# Sheet1.net
KiCad netlist of a schematic drawn in Altium Designer
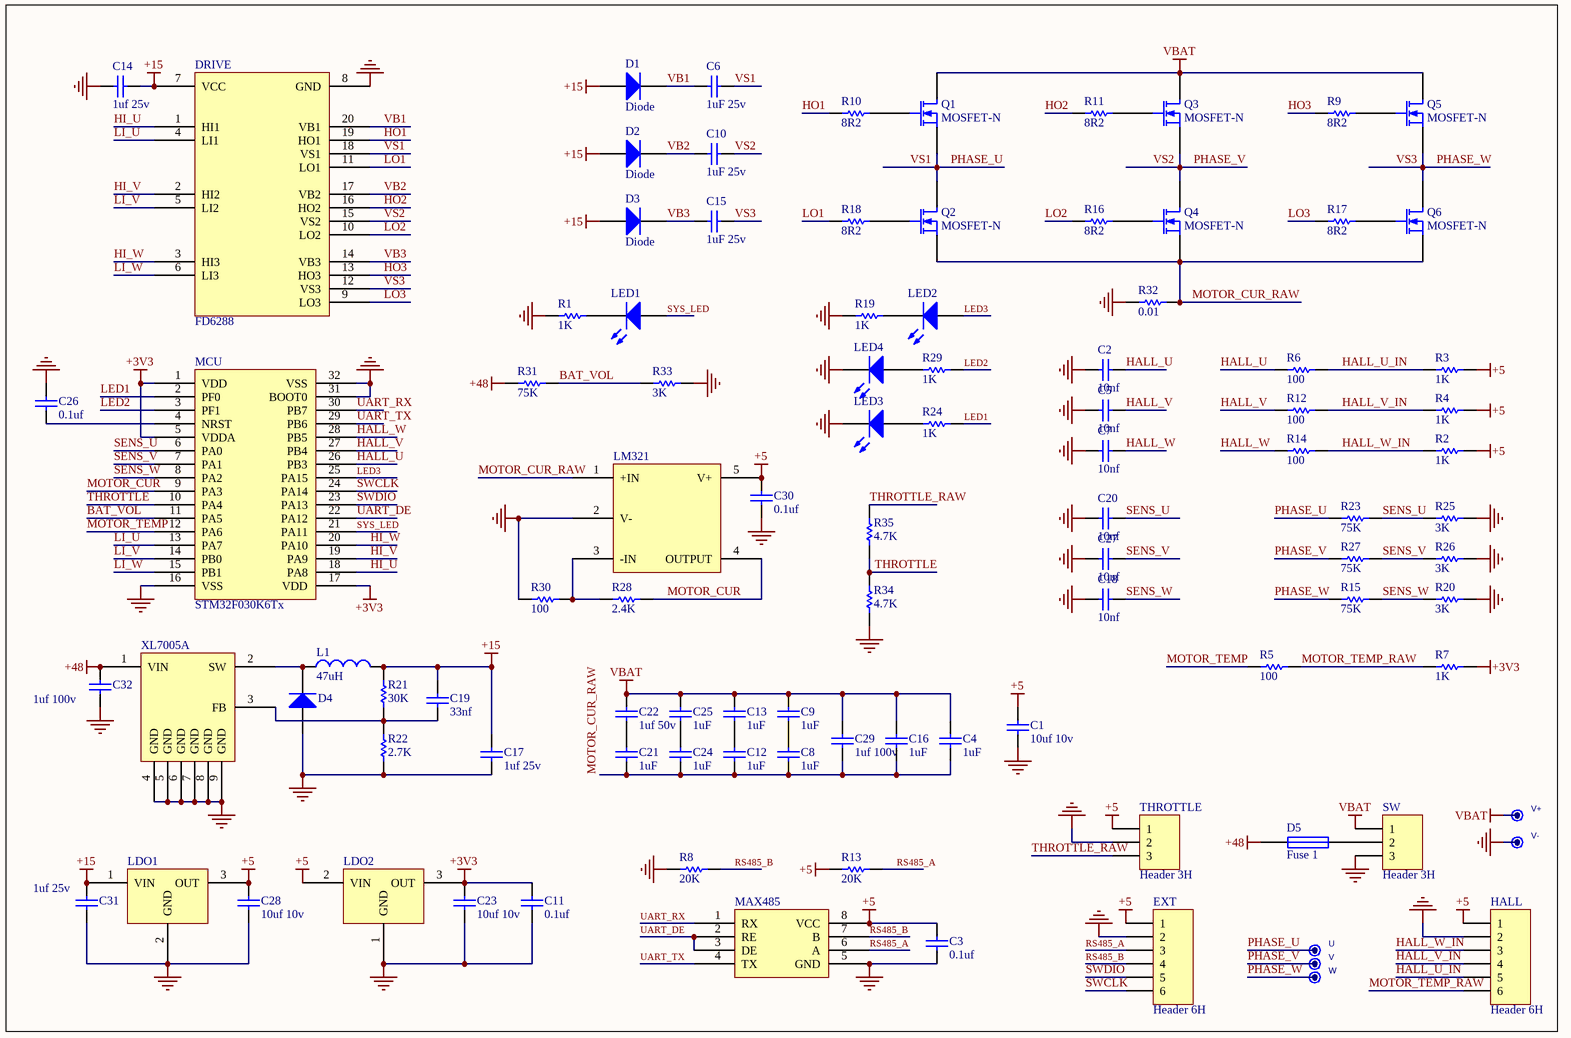
[diagram p0: Sheet1.SchDoc]

(export (version "E")
  (design (tool "Eeschema 10.0.6"))
  (components
    (comp (ref "C1")
      (value "10uf 10v")
      (footprint "0603")
      (description "Capacitor")
      (fields (field (name "Comment") "Cap") (field (name "PUBLISHER") "Altium Limited"))
      (libsource (lib "Miscellaneous Devices") (part "Cap"))
    )
    (comp (ref "C2")
      (value "10nf")
      (footprint "0603")
      (description "Capacitor")
      (fields (field (name "Comment") "Cap") (field (name "PUBLISHER") "Altium Limited"))
      (libsource (lib "Miscellaneous Devices") (part "Cap"))
    )
    (comp (ref "C3")
      (value "0.1uf")
      (footprint "0603")
      (description "Capacitor")
      (fields (field (name "Comment") "Cap") (field (name "PUBLISHER") "Altium Limited"))
      (libsource (lib "Miscellaneous Devices") (part "Cap"))
    )
    (comp (ref "C4")
      (value "1uF")
      (footprint "0603")
      (description "Capacitor")
      (fields (field (name "Comment") "Cap") (field (name "PUBLISHER") "Altium Limited"))
      (libsource (lib "Miscellaneous Devices") (part "Cap"))
    )
    (comp (ref "C5")
      (value "10nf")
      (footprint "0603")
      (description "Capacitor")
      (fields (field (name "Comment") "Cap") (field (name "PUBLISHER") "Altium Limited"))
      (libsource (lib "Miscellaneous Devices") (part "Cap"))
    )
    (comp (ref "C6")
      (value "1uF 25v")
      (footprint "0603")
      (description "Capacitor")
      (fields (field (name "Comment") "Cap") (field (name "PUBLISHER") "Altium Limited"))
      (libsource (lib "Miscellaneous Devices") (part "Cap"))
    )
    (comp (ref "C7")
      (value "10nf")
      (footprint "0603")
      (description "Capacitor")
      (fields (field (name "Comment") "Cap") (field (name "PUBLISHER") "Altium Limited"))
      (libsource (lib "Miscellaneous Devices") (part "Cap"))
    )
    (comp (ref "C8")
      (value "1uF")
      (footprint "1206")
      (description "Capacitor")
      (fields (field (name "Comment") "Cap") (field (name "PUBLISHER") "Altium Limited"))
      (libsource (lib "Miscellaneous Devices") (part "Cap"))
    )
    (comp (ref "C9")
      (value "1uF")
      (footprint "1206")
      (description "Capacitor")
      (fields (field (name "Comment") "Cap") (field (name "PUBLISHER") "Altium Limited"))
      (libsource (lib "Miscellaneous Devices") (part "Cap"))
    )
    (comp (ref "C10")
      (value "1uF 25v")
      (footprint "0603")
      (description "Capacitor")
      (fields (field (name "Comment") "Cap") (field (name "PUBLISHER") "Altium Limited"))
      (libsource (lib "Miscellaneous Devices") (part "Cap"))
    )
    (comp (ref "C11")
      (value "0.1uf")
      (footprint "0603")
      (description "Capacitor")
      (fields (field (name "Comment") "Cap") (field (name "PUBLISHER") "Altium Limited"))
      (libsource (lib "Miscellaneous Devices") (part "Cap"))
    )
    (comp (ref "C12")
      (value "1uF")
      (footprint "1206")
      (description "Capacitor")
      (fields (field (name "Comment") "Cap") (field (name "PUBLISHER") "Altium Limited"))
      (libsource (lib "Miscellaneous Devices") (part "Cap"))
    )
    (comp (ref "C13")
      (value "1uF")
      (footprint "1206")
      (description "Capacitor")
      (fields (field (name "Comment") "Cap") (field (name "PUBLISHER") "Altium Limited"))
      (libsource (lib "Miscellaneous Devices") (part "Cap"))
    )
    (comp (ref "C14")
      (value "1uf 25v")
      (footprint "0603")
      (description "Capacitor")
      (fields (field (name "Comment") "Cap") (field (name "PUBLISHER") "Altium Limited"))
      (libsource (lib "Miscellaneous Devices") (part "Cap"))
    )
    (comp (ref "C15")
      (value "1uF 25v")
      (footprint "0603")
      (description "Capacitor")
      (fields (field (name "Comment") "Cap") (field (name "PUBLISHER") "Altium Limited"))
      (libsource (lib "Miscellaneous Devices") (part "Cap"))
    )
    (comp (ref "C16")
      (value "1uF")
      (footprint "0603")
      (description "Capacitor")
      (fields (field (name "Comment") "Cap") (field (name "PUBLISHER") "Altium Limited"))
      (libsource (lib "Miscellaneous Devices") (part "Cap"))
    )
    (comp (ref "C17")
      (value "1uf 25v")
      (footprint "0603")
      (description "Capacitor")
      (fields (field (name "Comment") "Cap") (field (name "PUBLISHER") "Altium Limited"))
      (libsource (lib "Miscellaneous Devices") (part "Cap"))
    )
    (comp (ref "C18")
      (value "10nf")
      (footprint "0603")
      (description "Capacitor")
      (fields (field (name "Comment") "Cap") (field (name "PUBLISHER") "Altium Limited"))
      (libsource (lib "Miscellaneous Devices") (part "Cap"))
    )
    (comp (ref "C19")
      (value "33nf")
      (footprint "0603")
      (description "Capacitor")
      (fields (field (name "Comment") "Cap") (field (name "PUBLISHER") "Altium Limited"))
      (libsource (lib "Miscellaneous Devices") (part "Cap"))
    )
    (comp (ref "C20")
      (value "10nf")
      (footprint "0603")
      (description "Capacitor")
      (fields (field (name "Comment") "Cap") (field (name "PUBLISHER") "Altium Limited"))
      (libsource (lib "Miscellaneous Devices") (part "Cap"))
    )
    (comp (ref "C21")
      (value "1uF")
      (footprint "1206")
      (description "Capacitor")
      (fields (field (name "Comment") "Cap") (field (name "PUBLISHER") "Altium Limited"))
      (libsource (lib "Miscellaneous Devices") (part "Cap"))
    )
    (comp (ref "C22")
      (value "1uf 50v")
      (footprint "1206")
      (description "Capacitor")
      (fields (field (name "Comment") "Cap") (field (name "PUBLISHER") "Altium Limited"))
      (libsource (lib "Miscellaneous Devices") (part "Cap"))
    )
    (comp (ref "C23")
      (value "10uf 10v")
      (footprint "0603")
      (description "Capacitor")
      (fields (field (name "Comment") "Cap") (field (name "PUBLISHER") "Altium Limited"))
      (libsource (lib "Miscellaneous Devices") (part "Cap"))
    )
    (comp (ref "C24")
      (value "1uF")
      (footprint "1206")
      (description "Capacitor")
      (fields (field (name "Comment") "Cap") (field (name "PUBLISHER") "Altium Limited"))
      (libsource (lib "Miscellaneous Devices") (part "Cap"))
    )
    (comp (ref "C25")
      (value "1uF")
      (footprint "1206")
      (description "Capacitor")
      (fields (field (name "Comment") "Cap") (field (name "PUBLISHER") "Altium Limited"))
      (libsource (lib "Miscellaneous Devices") (part "Cap"))
    )
    (comp (ref "C26")
      (value "0.1uf")
      (footprint "0603")
      (description "Capacitor")
      (fields (field (name "Comment") "Cap") (field (name "PUBLISHER") "Altium Limited"))
      (libsource (lib "Miscellaneous Devices") (part "Cap"))
    )
    (comp (ref "C27")
      (value "10nf")
      (footprint "0603")
      (description "Capacitor")
      (fields (field (name "Comment") "Cap") (field (name "PUBLISHER") "Altium Limited"))
      (libsource (lib "Miscellaneous Devices") (part "Cap"))
    )
    (comp (ref "C28")
      (value "10uf 10v")
      (footprint "0603")
      (description "Capacitor")
      (fields (field (name "Comment") "Cap") (field (name "PUBLISHER") "Altium Limited"))
      (libsource (lib "Miscellaneous Devices") (part "Cap"))
    )
    (comp (ref "C29")
      (value "1uf 100v")
      (footprint "0603")
      (description "Capacitor")
      (fields (field (name "Comment") "Cap") (field (name "PUBLISHER") "Altium Limited"))
      (libsource (lib "Miscellaneous Devices") (part "Cap"))
    )
    (comp (ref "C30")
      (value "0.1uf")
      (footprint "0603")
      (description "Capacitor")
      (fields (field (name "Comment") "Cap") (field (name "PUBLISHER") "Altium Limited"))
      (libsource (lib "Miscellaneous Devices") (part "Cap"))
    )
    (comp (ref "C31")
      (value "1uf 25v")
      (footprint "0603")
      (description "Capacitor")
      (fields (field (name "Comment") "Cap") (field (name "PUBLISHER") "Altium Limited"))
      (libsource (lib "Miscellaneous Devices") (part "Cap"))
    )
    (comp (ref "C32")
      (value "1uf 100v")
      (footprint "1206")
      (description "Capacitor")
      (fields (field (name "Comment") "Cap") (field (name "PUBLISHER") "Altium Limited"))
      (libsource (lib "Miscellaneous Devices") (part "Cap"))
    )
    (comp (ref "D1")
      (value "Diode")
      (footprint "0603")
      (description "Default Diode")
      (fields (field (name "PUBLISHER") "Altium Limited"))
      (libsource (lib "Miscellaneous Devices") (part "Diode"))
    )
    (comp (ref "D2")
      (value "Diode")
      (footprint "0603")
      (description "Default Diode")
      (fields (field (name "PUBLISHER") "Altium Limited"))
      (libsource (lib "Miscellaneous Devices") (part "Diode"))
    )
    (comp (ref "D3")
      (value "Diode")
      (footprint "0603")
      (description "Default Diode")
      (fields (field (name "PUBLISHER") "Altium Limited"))
      (libsource (lib "Miscellaneous Devices") (part "Diode"))
    )
    (comp (ref "D4")
      (value "Diode")
      (footprint "1206")
      (description "Default Diode")
      (fields (field (name "PUBLISHER") "Altium Limited"))
      (libsource (lib "Miscellaneous Devices") (part "Diode"))
    )
    (comp (ref "D5")
      (value "Fuse 1")
      (footprint "1206")
      (description "Fuse")
      (fields (field (name "PUBLISHER") "Altium Limited"))
      (libsource (lib "Miscellaneous Devices") (part "Fuse 1"))
    )
    (comp (ref "DRIVE") (value "FD6288") (footprint "TSSOP20") (libsource (lib "Schlib1") (part "FD6288")))
    (comp (ref "EXT")
      (value "Header 6H")
      (footprint "HDR1X6H")
      (description "Header, 6-Pin, Right Angle")
      (fields (field (name "PUBLISHER") "Altium Limited"))
      (libsource (lib "Miscellaneous Connectors") (part "Header 6H"))
    )
    (comp (ref "HALL")
      (value "Header 6H")
      (footprint "HDR1X6H")
      (description "Header, 6-Pin, Right Angle")
      (fields (field (name "PUBLISHER") "Altium Limited"))
      (libsource (lib "Miscellaneous Connectors") (part "Header 6H"))
    )
    (comp (ref "L1")
      (value "47uH")
      (footprint "CDRH3D16")
      (description "Inductor")
      (fields (field (name "PUBLISHER") "Altium Limited"))
      (libsource (lib "Miscellaneous Devices") (part "Inductor"))
    )
    (comp (ref "LDO1") (value "78L05") (footprint "SOT-89") (libsource (lib "Schlib1") (part "78L05")))
    (comp (ref "LDO2") (value "XC6206") (footprint "SOT23") (libsource (lib "Schlib1") (part "HT75xx")))
    (comp (ref "LED1")
      (value "LED0")
      (footprint "0603")
      (description "Typical INFRARED GaAs LED")
      (fields (field (name "PUBLISHER") "Altium Limited"))
      (libsource (lib "Miscellaneous Devices") (part "LED0"))
    )
    (comp (ref "LED2")
      (value "LED0")
      (footprint "0603")
      (description "Typical INFRARED GaAs LED")
      (fields (field (name "PUBLISHER") "Altium Limited"))
      (libsource (lib "Miscellaneous Devices") (part "LED0"))
    )
    (comp (ref "LED3")
      (value "LED0")
      (footprint "0603")
      (description "Typical INFRARED GaAs LED")
      (fields (field (name "PUBLISHER") "Altium Limited"))
      (libsource (lib "Miscellaneous Devices") (part "LED0"))
    )
    (comp (ref "LED4")
      (value "LED0")
      (footprint "0603")
      (description "Typical INFRARED GaAs LED")
      (fields (field (name "PUBLISHER") "Altium Limited"))
      (libsource (lib "Miscellaneous Devices") (part "LED0"))
    )
    (comp (ref "LM321") (value "LM321") (footprint "SOT23-5") (libsource (lib "Schlib1") (part "LM321")))
    (comp (ref "MAX485") (value "MAX485") (footprint "SOIC-8") (libsource (lib "Schlib1") (part "SP3485")))
    (comp (ref "MCU")
      (value "STM32F030K6Tx")
      (footprint "LQFP-32")
      (libsource (lib "Schlib1") (part "STM32F030K6Tx"))
    )
    (comp (ref "Q1")
      (value "MOSFET-N")
      (footprint "TO220-MIX")
      (description "N-Channel MOSFET")
      (fields (field (name "PUBLISHER") "Altium Limited"))
      (libsource (lib "Miscellaneous Devices") (part "MOSFET-N"))
    )
    (comp (ref "Q2")
      (value "MOSFET-N")
      (footprint "TO220-MIX")
      (description "N-Channel MOSFET")
      (fields (field (name "PUBLISHER") "Altium Limited"))
      (libsource (lib "Miscellaneous Devices") (part "MOSFET-N"))
    )
    (comp (ref "Q3")
      (value "MOSFET-N")
      (footprint "TO220-MIX")
      (description "N-Channel MOSFET")
      (fields (field (name "PUBLISHER") "Altium Limited"))
      (libsource (lib "Miscellaneous Devices") (part "MOSFET-N"))
    )
    (comp (ref "Q4")
      (value "MOSFET-N")
      (footprint "TO220-MIX")
      (description "N-Channel MOSFET")
      (fields (field (name "PUBLISHER") "Altium Limited"))
      (libsource (lib "Miscellaneous Devices") (part "MOSFET-N"))
    )
    (comp (ref "Q5")
      (value "MOSFET-N")
      (footprint "TO220-MIX")
      (description "N-Channel MOSFET")
      (fields (field (name "PUBLISHER") "Altium Limited"))
      (libsource (lib "Miscellaneous Devices") (part "MOSFET-N"))
    )
    (comp (ref "Q6")
      (value "MOSFET-N")
      (footprint "TO220-MIX")
      (description "N-Channel MOSFET")
      (fields (field (name "PUBLISHER") "Altium Limited"))
      (libsource (lib "Miscellaneous Devices") (part "MOSFET-N"))
    )
    (comp (ref "R1")
      (value "1K")
      (footprint "0603")
      (description "Resistor")
      (fields (field (name "Comment") "Res1") (field (name "PUBLISHER") "Altium Limited"))
      (libsource (lib "Miscellaneous Devices") (part "Res1"))
    )
    (comp (ref "R2")
      (value "1K")
      (footprint "0603")
      (description "Resistor")
      (fields (field (name "Comment") "Res1") (field (name "PUBLISHER") "Altium Limited"))
      (libsource (lib "Miscellaneous Devices") (part "Res1"))
    )
    (comp (ref "R3")
      (value "1K")
      (footprint "0603")
      (description "Resistor")
      (fields (field (name "Comment") "Res1") (field (name "PUBLISHER") "Altium Limited"))
      (libsource (lib "Miscellaneous Devices") (part "Res1"))
    )
    (comp (ref "R4")
      (value "1K")
      (footprint "0603")
      (description "Resistor")
      (fields (field (name "Comment") "Res1") (field (name "PUBLISHER") "Altium Limited"))
      (libsource (lib "Miscellaneous Devices") (part "Res1"))
    )
    (comp (ref "R5")
      (value "100")
      (footprint "0603")
      (description "Resistor")
      (fields (field (name "Comment") "Res1") (field (name "PUBLISHER") "Altium Limited"))
      (libsource (lib "Miscellaneous Devices") (part "Res1"))
    )
    (comp (ref "R6")
      (value "100")
      (footprint "0603")
      (description "Resistor")
      (fields (field (name "Comment") "Res1") (field (name "PUBLISHER") "Altium Limited"))
      (libsource (lib "Miscellaneous Devices") (part "Res1"))
    )
    (comp (ref "R7")
      (value "1K")
      (footprint "0603")
      (description "Resistor")
      (fields (field (name "Comment") "Res1") (field (name "PUBLISHER") "Altium Limited"))
      (libsource (lib "Miscellaneous Devices") (part "Res1"))
    )
    (comp (ref "R8")
      (value "20K")
      (footprint "0603")
      (description "Resistor")
      (fields (field (name "Comment") "Res1") (field (name "PUBLISHER") "Altium Limited"))
      (libsource (lib "Miscellaneous Devices") (part "Res1"))
    )
    (comp (ref "R9")
      (value "8R2")
      (footprint "0603")
      (description "Resistor")
      (fields (field (name "Comment") "Res1") (field (name "PUBLISHER") "Altium Limited"))
      (libsource (lib "Miscellaneous Devices") (part "Res1"))
    )
    (comp (ref "R10")
      (value "8R2")
      (footprint "0603")
      (description "Resistor")
      (fields (field (name "Comment") "Res1") (field (name "PUBLISHER") "Altium Limited"))
      (libsource (lib "Miscellaneous Devices") (part "Res1"))
    )
    (comp (ref "R11")
      (value "8R2")
      (footprint "0603")
      (description "Resistor")
      (fields (field (name "Comment") "Res1") (field (name "PUBLISHER") "Altium Limited"))
      (libsource (lib "Miscellaneous Devices") (part "Res1"))
    )
    (comp (ref "R12")
      (value "100")
      (footprint "0603")
      (description "Resistor")
      (fields (field (name "Comment") "Res1") (field (name "PUBLISHER") "Altium Limited"))
      (libsource (lib "Miscellaneous Devices") (part "Res1"))
    )
    (comp (ref "R13")
      (value "20K")
      (footprint "0603")
      (description "Resistor")
      (fields (field (name "Comment") "Res1") (field (name "PUBLISHER") "Altium Limited"))
      (libsource (lib "Miscellaneous Devices") (part "Res1"))
    )
    (comp (ref "R14")
      (value "100")
      (footprint "0603")
      (description "Resistor")
      (fields (field (name "Comment") "Res1") (field (name "PUBLISHER") "Altium Limited"))
      (libsource (lib "Miscellaneous Devices") (part "Res1"))
    )
    (comp (ref "R15")
      (value "75K")
      (footprint "0603")
      (description "Resistor")
      (fields (field (name "Comment") "Res1") (field (name "PUBLISHER") "Altium Limited"))
      (libsource (lib "Miscellaneous Devices") (part "Res1"))
    )
    (comp (ref "R16")
      (value "8R2")
      (footprint "0603")
      (description "Resistor")
      (fields (field (name "Comment") "Res1") (field (name "PUBLISHER") "Altium Limited"))
      (libsource (lib "Miscellaneous Devices") (part "Res1"))
    )
    (comp (ref "R17")
      (value "8R2")
      (footprint "0603")
      (description "Resistor")
      (fields (field (name "Comment") "Res1") (field (name "PUBLISHER") "Altium Limited"))
      (libsource (lib "Miscellaneous Devices") (part "Res1"))
    )
    (comp (ref "R18")
      (value "8R2")
      (footprint "0603")
      (description "Resistor")
      (fields (field (name "Comment") "Res1") (field (name "PUBLISHER") "Altium Limited"))
      (libsource (lib "Miscellaneous Devices") (part "Res1"))
    )
    (comp (ref "R19")
      (value "1K")
      (footprint "0603")
      (description "Resistor")
      (fields (field (name "Comment") "Res1") (field (name "PUBLISHER") "Altium Limited"))
      (libsource (lib "Miscellaneous Devices") (part "Res1"))
    )
    (comp (ref "R20")
      (value "3K")
      (footprint "0603")
      (description "Resistor")
      (fields (field (name "Comment") "Res1") (field (name "PUBLISHER") "Altium Limited"))
      (libsource (lib "Miscellaneous Devices") (part "Res1"))
    )
    (comp (ref "R21")
      (value "30K")
      (footprint "0603")
      (description "Resistor")
      (fields (field (name "Comment") "Res1") (field (name "PUBLISHER") "Altium Limited"))
      (libsource (lib "Miscellaneous Devices") (part "Res1"))
    )
    (comp (ref "R22")
      (value "2.7K")
      (footprint "0603")
      (description "Resistor")
      (fields (field (name "Comment") "Res1") (field (name "PUBLISHER") "Altium Limited"))
      (libsource (lib "Miscellaneous Devices") (part "Res1"))
    )
    (comp (ref "R23")
      (value "75K")
      (footprint "0603")
      (description "Resistor")
      (fields (field (name "Comment") "Res1") (field (name "PUBLISHER") "Altium Limited"))
      (libsource (lib "Miscellaneous Devices") (part "Res1"))
    )
    (comp (ref "R24")
      (value "1K")
      (footprint "0603")
      (description "Resistor")
      (fields (field (name "Comment") "Res1") (field (name "PUBLISHER") "Altium Limited"))
      (libsource (lib "Miscellaneous Devices") (part "Res1"))
    )
    (comp (ref "R25")
      (value "3K")
      (footprint "0603")
      (description "Resistor")
      (fields (field (name "Comment") "Res1") (field (name "PUBLISHER") "Altium Limited"))
      (libsource (lib "Miscellaneous Devices") (part "Res1"))
    )
    (comp (ref "R26")
      (value "3K")
      (footprint "0603")
      (description "Resistor")
      (fields (field (name "Comment") "Res1") (field (name "PUBLISHER") "Altium Limited"))
      (libsource (lib "Miscellaneous Devices") (part "Res1"))
    )
    (comp (ref "R27")
      (value "75K")
      (footprint "0603")
      (description "Resistor")
      (fields (field (name "Comment") "Res1") (field (name "PUBLISHER") "Altium Limited"))
      (libsource (lib "Miscellaneous Devices") (part "Res1"))
    )
    (comp (ref "R28")
      (value "2.4K")
      (footprint "0603")
      (description "Resistor")
      (fields (field (name "Comment") "Res1") (field (name "PUBLISHER") "Altium Limited"))
      (libsource (lib "Miscellaneous Devices") (part "Res1"))
    )
    (comp (ref "R29")
      (value "1K")
      (footprint "0603")
      (description "Resistor")
      (fields (field (name "Comment") "Res1") (field (name "PUBLISHER") "Altium Limited"))
      (libsource (lib "Miscellaneous Devices") (part "Res1"))
    )
    (comp (ref "R30")
      (value "100")
      (footprint "0603")
      (description "Resistor")
      (fields (field (name "Comment") "Res1") (field (name "PUBLISHER") "Altium Limited"))
      (libsource (lib "Miscellaneous Devices") (part "Res1"))
    )
    (comp (ref "R31")
      (value "75K")
      (footprint "0603")
      (description "Resistor")
      (fields (field (name "Comment") "Res1") (field (name "PUBLISHER") "Altium Limited"))
      (libsource (lib "Miscellaneous Devices") (part "Res1"))
    )
    (comp (ref "R32")
      (value "0.01")
      (footprint "1206")
      (description "Resistor")
      (fields (field (name "Comment") "Res1") (field (name "PUBLISHER") "Altium Limited"))
      (libsource (lib "Miscellaneous Devices") (part "Res1"))
    )
    (comp (ref "R33")
      (value "3K")
      (footprint "0603")
      (description "Resistor")
      (fields (field (name "Comment") "Res1") (field (name "PUBLISHER") "Altium Limited"))
      (libsource (lib "Miscellaneous Devices") (part "Res1"))
    )
    (comp (ref "R34")
      (value "4.7K")
      (footprint "0603")
      (description "Resistor")
      (fields (field (name "Comment") "Res1") (field (name "PUBLISHER") "Altium Limited"))
      (libsource (lib "Miscellaneous Devices") (part "Res1"))
    )
    (comp (ref "R35")
      (value "4.7K")
      (footprint "0603")
      (description "Resistor")
      (fields (field (name "Comment") "Res1") (field (name "PUBLISHER") "Altium Limited"))
      (libsource (lib "Miscellaneous Devices") (part "Res1"))
    )
    (comp (ref "SW")
      (value "Header 3H")
      (footprint "HDR1X3H")
      (description "Header, 3-Pin, Right Angle")
      (fields (field (name "PUBLISHER") "Altium Limited"))
      (libsource (lib "Miscellaneous Connectors") (part "Header 3H"))
    )
    (comp (ref "THROTTLE")
      (value "Header 3H")
      (footprint "HDR1X3H")
      (description "Header, 3-Pin, Right Angle")
      (fields (field (name "PUBLISHER") "Altium Limited"))
      (libsource (lib "Miscellaneous Connectors") (part "Header 3H"))
    )
    (comp (ref "U")
      (value "TPS50mil")
      (footprint "PHASE")
      (description "Test Point, 12x25mil, Not Populated")
      (libsource (lib "mis") (part "TPS50mil"))
    )
    (comp (ref "V")
      (value "TPS50mil")
      (footprint "PHASE")
      (description "Test Point, 12x25mil, Not Populated")
      (libsource (lib "mis") (part "TPS50mil"))
    )
    (comp (ref "V+")
      (value "TPS50mil")
      (footprint "PHASE")
      (description "Test Point, 12x25mil, Not Populated")
      (libsource (lib "mis") (part "TPS50mil"))
    )
    (comp (ref "V-")
      (value "TPS50mil")
      (footprint "PHASE")
      (description "Test Point, 12x25mil, Not Populated")
      (libsource (lib "mis") (part "TPS50mil"))
    )
    (comp (ref "W")
      (value "TPS50mil")
      (footprint "PHASE")
      (description "Test Point, 12x25mil, Not Populated")
      (libsource (lib "mis") (part "TPS50mil"))
    )
    (comp (ref "XL7005A")
      (value "XL7005A")
      (footprint "SOIC-8P")
      (libsource (lib "Schlib1") (part "XL7005A"))
    )
  )
  (nets
    (net (code "1") (name "+3V3") (class "Default")
      (node (ref "C11") (pin "1") (pinfunction "1_1") (pintype "passive"))
      (node (ref "C23") (pin "1") (pinfunction "1_1") (pintype "passive"))
      (node (ref "LDO2") (pin "3") (pinfunction "OUT_3") (pintype "passive"))
      (node (ref "MCU") (pin "1") (pinfunction "VDD_1") (pintype "passive"))
      (node (ref "MCU") (pin "17") (pinfunction "VDD_17") (pintype "passive"))
      (node (ref "MCU") (pin "5") (pinfunction "VDDA_5") (pintype "passive"))
      (node (ref "R7") (pin "1") (pinfunction "1_1") (pintype "passive"))
    )
    (net (code "2") (name "+5") (class "Default")
      (node (ref "C1") (pin "1") (pinfunction "1_1") (pintype "passive"))
      (node (ref "C28") (pin "1") (pinfunction "1_1") (pintype "passive"))
      (node (ref "C3") (pin "1") (pinfunction "1_1") (pintype "passive"))
      (node (ref "C30") (pin "1") (pinfunction "1_1") (pintype "passive"))
      (node (ref "EXT") (pin "1") (pinfunction "1_1") (pintype "passive"))
      (node (ref "HALL") (pin "1") (pinfunction "1_1") (pintype "passive"))
      (node (ref "LDO1") (pin "3") (pinfunction "OUT_3") (pintype "passive"))
      (node (ref "LDO2") (pin "2") (pinfunction "VIN_2") (pintype "passive"))
      (node (ref "LM321") (pin "5") (pinfunction "V+_5") (pintype "passive"))
      (node (ref "MAX485") (pin "8") (pinfunction "VCC_8") (pintype "passive"))
      (node (ref "R13") (pin "1") (pinfunction "1_1") (pintype "passive"))
      (node (ref "R2") (pin "1") (pinfunction "1_1") (pintype "passive"))
      (node (ref "R3") (pin "1") (pinfunction "1_1") (pintype "passive"))
      (node (ref "R4") (pin "1") (pinfunction "1_1") (pintype "passive"))
      (node (ref "THROTTLE") (pin "1") (pinfunction "1_1") (pintype "passive"))
    )
    (net (code "3") (name "+15") (class "Default")
      (node (ref "C14") (pin "2") (pinfunction "2_2") (pintype "passive"))
      (node (ref "C17") (pin "1") (pinfunction "1_1") (pintype "passive"))
      (node (ref "C19") (pin "1") (pinfunction "1_1") (pintype "passive"))
      (node (ref "C31") (pin "1") (pinfunction "1_1") (pintype "passive"))
      (node (ref "D1") (pin "1") (pinfunction "A_1") (pintype "passive"))
      (node (ref "D2") (pin "1") (pinfunction "A_1") (pintype "passive"))
      (node (ref "D3") (pin "1") (pinfunction "A_1") (pintype "passive"))
      (node (ref "DRIVE") (pin "7") (pinfunction "VCC_7") (pintype "passive"))
      (node (ref "L1") (pin "2") (pinfunction "2_2") (pintype "passive"))
      (node (ref "LDO1") (pin "1") (pinfunction "VIN_1") (pintype "passive"))
      (node (ref "R21") (pin "1") (pinfunction "1_1") (pintype "passive"))
    )
    (net (code "4") (name "+48") (class "Default")
      (node (ref "C32") (pin "1") (pinfunction "1_1") (pintype "passive"))
      (node (ref "D5") (pin "1") (pinfunction "1_1") (pintype "passive"))
      (node (ref "R31") (pin "1") (pinfunction "1_1") (pintype "passive"))
      (node (ref "XL7005A") (pin "1") (pinfunction "VIN_1") (pintype "passive"))
    )
    (net (code "5") (name "/BAT_VOL") (class "Default")
      (node (ref "MCU") (pin "11") (pinfunction "PA5_11") (pintype "passive"))
      (node (ref "R31") (pin "2") (pinfunction "2_2") (pintype "passive"))
      (node (ref "R33") (pin "1") (pinfunction "1_1") (pintype "passive"))
    )
    (net (code "6") (name "/HALL_U") (class "Default")
      (node (ref "C2") (pin "1") (pinfunction "1_1") (pintype "passive"))
      (node (ref "MCU") (pin "26") (pinfunction "PB3_26") (pintype "passive"))
      (node (ref "R6") (pin "2") (pinfunction "2_2") (pintype "passive"))
    )
    (net (code "7") (name "/HALL_U_IN") (class "Default")
      (node (ref "HALL") (pin "5") (pinfunction "5_5") (pintype "passive"))
      (node (ref "R3") (pin "2") (pinfunction "2_2") (pintype "passive"))
      (node (ref "R6") (pin "1") (pinfunction "1_1") (pintype "passive"))
    )
    (net (code "8") (name "/HALL_V") (class "Default")
      (node (ref "C5") (pin "1") (pinfunction "1_1") (pintype "passive"))
      (node (ref "MCU") (pin "27") (pinfunction "PB4_27") (pintype "passive"))
      (node (ref "R12") (pin "2") (pinfunction "2_2") (pintype "passive"))
    )
    (net (code "9") (name "/HALL_V_IN") (class "Default")
      (node (ref "HALL") (pin "4") (pinfunction "4_4") (pintype "passive"))
      (node (ref "R12") (pin "1") (pinfunction "1_1") (pintype "passive"))
      (node (ref "R4") (pin "2") (pinfunction "2_2") (pintype "passive"))
    )
    (net (code "10") (name "/HALL_W") (class "Default")
      (node (ref "C7") (pin "1") (pinfunction "1_1") (pintype "passive"))
      (node (ref "MCU") (pin "28") (pinfunction "PB5_28") (pintype "passive"))
      (node (ref "R14") (pin "2") (pinfunction "2_2") (pintype "passive"))
    )
    (net (code "11") (name "/HALL_W_IN") (class "Default")
      (node (ref "HALL") (pin "3") (pinfunction "3_3") (pintype "passive"))
      (node (ref "R14") (pin "1") (pinfunction "1_1") (pintype "passive"))
      (node (ref "R2") (pin "2") (pinfunction "2_2") (pintype "passive"))
    )
    (net (code "12") (name "/HI_U") (class "Default")
      (node (ref "DRIVE") (pin "1") (pinfunction "HI1_1") (pintype "passive"))
      (node (ref "MCU") (pin "18") (pinfunction "PA8_18") (pintype "passive"))
    )
    (net (code "13") (name "/HI_V") (class "Default")
      (node (ref "DRIVE") (pin "2") (pinfunction "HI2_2") (pintype "passive"))
      (node (ref "MCU") (pin "19") (pinfunction "PA9_19") (pintype "passive"))
    )
    (net (code "14") (name "/HI_W") (class "Default")
      (node (ref "DRIVE") (pin "3") (pinfunction "HI3_3") (pintype "passive"))
      (node (ref "MCU") (pin "20") (pinfunction "PA10_20") (pintype "passive"))
    )
    (net (code "15") (name "/HO1") (class "Default")
      (node (ref "DRIVE") (pin "19") (pinfunction "HO1_19") (pintype "passive"))
      (node (ref "R10") (pin "2") (pinfunction "2_2") (pintype "passive"))
    )
    (net (code "16") (name "/HO2") (class "Default")
      (node (ref "DRIVE") (pin "16") (pinfunction "HO2_16") (pintype "passive"))
      (node (ref "R11") (pin "2") (pinfunction "2_2") (pintype "passive"))
    )
    (net (code "17") (name "/HO3") (class "Default")
      (node (ref "DRIVE") (pin "13") (pinfunction "HO3_13") (pintype "passive"))
      (node (ref "R9") (pin "2") (pinfunction "2_2") (pintype "passive"))
    )
    (net (code "18") (name "/LED1") (class "Default")
      (node (ref "MCU") (pin "2") (pinfunction "PF0_2") (pintype "passive"))
      (node (ref "R24") (pin "1") (pinfunction "1_1") (pintype "passive"))
    )
    (net (code "19") (name "/LED2") (class "Default")
      (node (ref "MCU") (pin "3") (pinfunction "PF1_3") (pintype "passive"))
      (node (ref "R29") (pin "1") (pinfunction "1_1") (pintype "passive"))
    )
    (net (code "20") (name "/LED3") (class "Default")
      (node (ref "LED2") (pin "1") (pinfunction "A_1") (pintype "passive"))
      (node (ref "MCU") (pin "25") (pinfunction "PA15_25") (pintype "passive"))
    )
    (net (code "21") (name "/LI_U") (class "Default")
      (node (ref "DRIVE") (pin "4") (pinfunction "LI1_4") (pintype "passive"))
      (node (ref "MCU") (pin "13") (pinfunction "PA7_13") (pintype "passive"))
    )
    (net (code "22") (name "/LI_V") (class "Default")
      (node (ref "DRIVE") (pin "5") (pinfunction "LI2_5") (pintype "passive"))
      (node (ref "MCU") (pin "14") (pinfunction "PB0_14") (pintype "passive"))
    )
    (net (code "23") (name "/LI_W") (class "Default")
      (node (ref "DRIVE") (pin "6") (pinfunction "LI3_6") (pintype "passive"))
      (node (ref "MCU") (pin "15") (pinfunction "PB1_15") (pintype "passive"))
    )
    (net (code "24") (name "/LO1") (class "Default")
      (node (ref "DRIVE") (pin "11") (pinfunction "LO1_11") (pintype "passive"))
      (node (ref "R18") (pin "2") (pinfunction "2_2") (pintype "passive"))
    )
    (net (code "25") (name "/LO2") (class "Default")
      (node (ref "DRIVE") (pin "10") (pinfunction "LO2_10") (pintype "passive"))
      (node (ref "R16") (pin "2") (pinfunction "2_2") (pintype "passive"))
    )
    (net (code "26") (name "/LO3") (class "Default")
      (node (ref "DRIVE") (pin "9") (pinfunction "LO3_9") (pintype "passive"))
      (node (ref "R17") (pin "2") (pinfunction "2_2") (pintype "passive"))
    )
    (net (code "27") (name "/MOTOR_CUR") (class "Default")
      (node (ref "LM321") (pin "4") (pinfunction "OUTPUT_4") (pintype "passive"))
      (node (ref "MCU") (pin "9") (pinfunction "PA3_9") (pintype "passive"))
      (node (ref "R28") (pin "2") (pinfunction "2_2") (pintype "passive"))
    )
    (net (code "28") (name "/MOTOR_CUR_RAW") (class "Default")
      (node (ref "C12") (pin "2") (pinfunction "2_2") (pintype "passive"))
      (node (ref "C16") (pin "2") (pinfunction "2_2") (pintype "passive"))
      (node (ref "C21") (pin "2") (pinfunction "2_2") (pintype "passive"))
      (node (ref "C24") (pin "2") (pinfunction "2_2") (pintype "passive"))
      (node (ref "C29") (pin "2") (pinfunction "2_2") (pintype "passive"))
      (node (ref "C4") (pin "2") (pinfunction "2_2") (pintype "passive"))
      (node (ref "C8") (pin "2") (pinfunction "2_2") (pintype "passive"))
      (node (ref "LM321") (pin "1") (pinfunction "+IN_1") (pintype "passive"))
      (node (ref "Q2") (pin "3") (pinfunction "S_3") (pintype "passive"))
      (node (ref "Q4") (pin "3") (pinfunction "S_3") (pintype "passive"))
      (node (ref "Q6") (pin "3") (pinfunction "S_3") (pintype "passive"))
      (node (ref "R32") (pin "1") (pinfunction "1_1") (pintype "passive"))
    )
    (net (code "29") (name "/MOTOR_TEMP") (class "Default")
      (node (ref "MCU") (pin "12") (pinfunction "PA6_12") (pintype "passive"))
      (node (ref "R5") (pin "2") (pinfunction "2_2") (pintype "passive"))
    )
    (net (code "30") (name "/MOTOR_TEMP_RAW") (class "Default")
      (node (ref "HALL") (pin "6") (pinfunction "6_6") (pintype "passive"))
      (node (ref "R5") (pin "1") (pinfunction "1_1") (pintype "passive"))
      (node (ref "R7") (pin "2") (pinfunction "2_2") (pintype "passive"))
    )
    (net (code "31") (name "/PHASE_U") (class "Default")
      (node (ref "C6") (pin "1") (pinfunction "1_1") (pintype "passive"))
      (node (ref "DRIVE") (pin "18") (pinfunction "VS1_18") (pintype "passive"))
      (node (ref "Q1") (pin "3") (pinfunction "S_3") (pintype "passive"))
      (node (ref "Q2") (pin "1") (pinfunction "D_1") (pintype "passive"))
      (node (ref "R23") (pin "1") (pinfunction "1_1") (pintype "passive"))
      (node (ref "U") (pin "1") (pinfunction "1_1") (pintype "passive"))
    )
    (net (code "32") (name "/PHASE_V") (class "Default")
      (node (ref "C10") (pin "1") (pinfunction "1_1") (pintype "passive"))
      (node (ref "DRIVE") (pin "15") (pinfunction "VS2_15") (pintype "passive"))
      (node (ref "Q3") (pin "3") (pinfunction "S_3") (pintype "passive"))
      (node (ref "Q4") (pin "1") (pinfunction "D_1") (pintype "passive"))
      (node (ref "R27") (pin "1") (pinfunction "1_1") (pintype "passive"))
      (node (ref "V") (pin "1") (pinfunction "1_1") (pintype "passive"))
    )
    (net (code "33") (name "/PHASE_W") (class "Default")
      (node (ref "C15") (pin "1") (pinfunction "1_1") (pintype "passive"))
      (node (ref "DRIVE") (pin "12") (pinfunction "VS3_12") (pintype "passive"))
      (node (ref "Q5") (pin "3") (pinfunction "S_3") (pintype "passive"))
      (node (ref "Q6") (pin "1") (pinfunction "D_1") (pintype "passive"))
      (node (ref "R15") (pin "1") (pinfunction "1_1") (pintype "passive"))
      (node (ref "W") (pin "1") (pinfunction "1_1") (pintype "passive"))
    )
    (net (code "34") (name "/RS485_A") (class "Default")
      (node (ref "EXT") (pin "3") (pinfunction "3_3") (pintype "passive"))
      (node (ref "MAX485") (pin "6") (pinfunction "A_6") (pintype "passive"))
      (node (ref "R13") (pin "2") (pinfunction "2_2") (pintype "passive"))
    )
    (net (code "35") (name "/RS485_B") (class "Default")
      (node (ref "EXT") (pin "4") (pinfunction "4_4") (pintype "passive"))
      (node (ref "MAX485") (pin "7") (pinfunction "B_7") (pintype "passive"))
      (node (ref "R8") (pin "2") (pinfunction "2_2") (pintype "passive"))
    )
    (net (code "36") (name "/SENS_U") (class "Default")
      (node (ref "C20") (pin "2") (pinfunction "2_2") (pintype "passive"))
      (node (ref "MCU") (pin "6") (pinfunction "PA0_6") (pintype "passive"))
      (node (ref "R23") (pin "2") (pinfunction "2_2") (pintype "passive"))
      (node (ref "R25") (pin "1") (pinfunction "1_1") (pintype "passive"))
    )
    (net (code "37") (name "/SENS_V") (class "Default")
      (node (ref "C27") (pin "2") (pinfunction "2_2") (pintype "passive"))
      (node (ref "MCU") (pin "7") (pinfunction "PA1_7") (pintype "passive"))
      (node (ref "R26") (pin "1") (pinfunction "1_1") (pintype "passive"))
      (node (ref "R27") (pin "2") (pinfunction "2_2") (pintype "passive"))
    )
    (net (code "38") (name "/SENS_W") (class "Default")
      (node (ref "C18") (pin "2") (pinfunction "2_2") (pintype "passive"))
      (node (ref "MCU") (pin "8") (pinfunction "PA2_8") (pintype "passive"))
      (node (ref "R15") (pin "2") (pinfunction "2_2") (pintype "passive"))
      (node (ref "R20") (pin "1") (pinfunction "1_1") (pintype "passive"))
    )
    (net (code "39") (name "/SWCLK") (class "Default")
      (node (ref "EXT") (pin "6") (pinfunction "6_6") (pintype "passive"))
      (node (ref "MCU") (pin "24") (pinfunction "PA14_24") (pintype "passive"))
    )
    (net (code "40") (name "/SWDIO") (class "Default")
      (node (ref "EXT") (pin "5") (pinfunction "5_5") (pintype "passive"))
      (node (ref "MCU") (pin "23") (pinfunction "PA13_23") (pintype "passive"))
    )
    (net (code "41") (name "/SYS_LED") (class "Default")
      (node (ref "LED1") (pin "1") (pinfunction "A_1") (pintype "passive"))
      (node (ref "MCU") (pin "21") (pinfunction "PA11_21") (pintype "passive"))
    )
    (net (code "42") (name "/THROTTLE") (class "Default")
      (node (ref "MCU") (pin "10") (pinfunction "PA4_10") (pintype "passive"))
      (node (ref "R34") (pin "1") (pinfunction "1_1") (pintype "passive"))
      (node (ref "R35") (pin "2") (pinfunction "2_2") (pintype "passive"))
    )
    (net (code "43") (name "/THROTTLE_RAW") (class "Default")
      (node (ref "R35") (pin "1") (pinfunction "1_1") (pintype "passive"))
      (node (ref "THROTTLE") (pin "3") (pinfunction "3_3") (pintype "passive"))
    )
    (net (code "44") (name "/UART_DE") (class "Default")
      (node (ref "MAX485") (pin "2") (pinfunction "RE_2") (pintype "passive"))
      (node (ref "MAX485") (pin "3") (pinfunction "DE_3") (pintype "passive"))
      (node (ref "MCU") (pin "22") (pinfunction "PA12_22") (pintype "passive"))
    )
    (net (code "45") (name "/UART_RX") (class "Default")
      (node (ref "MAX485") (pin "1") (pinfunction "RX_1") (pintype "passive"))
      (node (ref "MCU") (pin "30") (pinfunction "PB7_30") (pintype "passive"))
    )
    (net (code "46") (name "/UART_TX") (class "Default")
      (node (ref "MAX485") (pin "4") (pinfunction "TX_4") (pintype "passive"))
      (node (ref "MCU") (pin "29") (pinfunction "PB6_29") (pintype "passive"))
    )
    (net (code "47") (name "/VB1") (class "Default")
      (node (ref "C6") (pin "2") (pinfunction "2_2") (pintype "passive"))
      (node (ref "D1") (pin "2") (pinfunction "K_2") (pintype "passive"))
      (node (ref "DRIVE") (pin "20") (pinfunction "VB1_20") (pintype "passive"))
    )
    (net (code "48") (name "/VB2") (class "Default")
      (node (ref "C10") (pin "2") (pinfunction "2_2") (pintype "passive"))
      (node (ref "D2") (pin "2") (pinfunction "K_2") (pintype "passive"))
      (node (ref "DRIVE") (pin "17") (pinfunction "VB2_17") (pintype "passive"))
    )
    (net (code "49") (name "/VB3") (class "Default")
      (node (ref "C15") (pin "2") (pinfunction "2_2") (pintype "passive"))
      (node (ref "D3") (pin "2") (pinfunction "K_2") (pintype "passive"))
      (node (ref "DRIVE") (pin "14") (pinfunction "VB3_14") (pintype "passive"))
    )
    (net (code "50") (name "GND") (class "Default")
      (node (ref "C1") (pin "2") (pinfunction "2_2") (pintype "passive"))
      (node (ref "C11") (pin "2") (pinfunction "2_2") (pintype "passive"))
      (node (ref "C14") (pin "1") (pinfunction "1_1") (pintype "passive"))
      (node (ref "C17") (pin "2") (pinfunction "2_2") (pintype "passive"))
      (node (ref "C18") (pin "1") (pinfunction "1_1") (pintype "passive"))
      (node (ref "C2") (pin "2") (pinfunction "2_2") (pintype "passive"))
      (node (ref "C20") (pin "1") (pinfunction "1_1") (pintype "passive"))
      (node (ref "C23") (pin "2") (pinfunction "2_2") (pintype "passive"))
      (node (ref "C26") (pin "1") (pinfunction "1_1") (pintype "passive"))
      (node (ref "C27") (pin "1") (pinfunction "1_1") (pintype "passive"))
      (node (ref "C28") (pin "2") (pinfunction "2_2") (pintype "passive"))
      (node (ref "C3") (pin "2") (pinfunction "2_2") (pintype "passive"))
      (node (ref "C30") (pin "2") (pinfunction "2_2") (pintype "passive"))
      (node (ref "C31") (pin "2") (pinfunction "2_2") (pintype "passive"))
      (node (ref "C32") (pin "2") (pinfunction "2_2") (pintype "passive"))
      (node (ref "C5") (pin "2") (pinfunction "2_2") (pintype "passive"))
      (node (ref "C7") (pin "2") (pinfunction "2_2") (pintype "passive"))
      (node (ref "D4") (pin "1") (pinfunction "A_1") (pintype "passive"))
      (node (ref "DRIVE") (pin "8") (pinfunction "GND_8") (pintype "passive"))
      (node (ref "EXT") (pin "2") (pinfunction "2_2") (pintype "passive"))
      (node (ref "HALL") (pin "2") (pinfunction "2_2") (pintype "passive"))
      (node (ref "LDO1") (pin "2") (pinfunction "GND_2") (pintype "passive"))
      (node (ref "LDO2") (pin "1") (pinfunction "GND_1") (pintype "passive"))
      (node (ref "LED3") (pin "2") (pinfunction "K_2") (pintype "passive"))
      (node (ref "LED4") (pin "2") (pinfunction "K_2") (pintype "passive"))
      (node (ref "LM321") (pin "2") (pinfunction "V-_2") (pintype "passive"))
      (node (ref "MAX485") (pin "5") (pinfunction "GND_5") (pintype "passive"))
      (node (ref "MCU") (pin "16") (pinfunction "VSS_16") (pintype "passive"))
      (node (ref "MCU") (pin "31") (pinfunction "BOOT0_31") (pintype "passive"))
      (node (ref "MCU") (pin "32") (pinfunction "VSS_32") (pintype "passive"))
      (node (ref "R1") (pin "2") (pinfunction "2_2") (pintype "passive"))
      (node (ref "R19") (pin "2") (pinfunction "2_2") (pintype "passive"))
      (node (ref "R20") (pin "2") (pinfunction "2_2") (pintype "passive"))
      (node (ref "R22") (pin "2") (pinfunction "2_2") (pintype "passive"))
      (node (ref "R25") (pin "2") (pinfunction "2_2") (pintype "passive"))
      (node (ref "R26") (pin "2") (pinfunction "2_2") (pintype "passive"))
      (node (ref "R30") (pin "1") (pinfunction "1_1") (pintype "passive"))
      (node (ref "R32") (pin "2") (pinfunction "2_2") (pintype "passive"))
      (node (ref "R33") (pin "2") (pinfunction "2_2") (pintype "passive"))
      (node (ref "R34") (pin "2") (pinfunction "2_2") (pintype "passive"))
      (node (ref "R8") (pin "1") (pinfunction "1_1") (pintype "passive"))
      (node (ref "SW") (pin "3") (pinfunction "3_3") (pintype "passive"))
      (node (ref "THROTTLE") (pin "2") (pinfunction "2_2") (pintype "passive"))
      (node (ref "V-") (pin "1") (pinfunction "1_1") (pintype "passive"))
      (node (ref "XL7005A") (pin "4") (pinfunction "GND_4") (pintype "passive"))
      (node (ref "XL7005A") (pin "5") (pinfunction "GND_5") (pintype "passive"))
      (node (ref "XL7005A") (pin "6") (pinfunction "GND_6") (pintype "passive"))
      (node (ref "XL7005A") (pin "7") (pinfunction "GND_7") (pintype "passive"))
      (node (ref "XL7005A") (pin "8") (pinfunction "GND_8") (pintype "passive"))
      (node (ref "XL7005A") (pin "9") (pinfunction "GND_9") (pintype "passive"))
    )
    (net (code "51") (name "Net-(C8-Pad1)") (class "Default")
      (node (ref "C8") (pin "1") (pinfunction "1_1") (pintype "passive"))
      (node (ref "C9") (pin "2") (pinfunction "2_2") (pintype "passive"))
    )
    (net (code "52") (name "Net-(C12-Pad1)") (class "Default")
      (node (ref "C12") (pin "1") (pinfunction "1_1") (pintype "passive"))
      (node (ref "C13") (pin "2") (pinfunction "2_2") (pintype "passive"))
    )
    (net (code "53") (name "Net-(C21-Pad1)") (class "Default")
      (node (ref "C21") (pin "1") (pinfunction "1_1") (pintype "passive"))
      (node (ref "C22") (pin "2") (pinfunction "2_2") (pintype "passive"))
    )
    (net (code "54") (name "Net-(C24-Pad1)") (class "Default")
      (node (ref "C24") (pin "1") (pinfunction "1_1") (pintype "passive"))
      (node (ref "C25") (pin "2") (pinfunction "2_2") (pintype "passive"))
    )
    (net (code "55") (name "Net-(D4-K)") (class "Default")
      (node (ref "D4") (pin "2") (pinfunction "K_2") (pintype "passive"))
      (node (ref "L1") (pin "1") (pinfunction "1_1") (pintype "passive"))
      (node (ref "XL7005A") (pin "2") (pinfunction "SW_2") (pintype "passive"))
    )
    (net (code "56") (name "Net-(D5-Pad2)") (class "Default")
      (node (ref "D5") (pin "2") (pinfunction "2_2") (pintype "passive"))
      (node (ref "SW") (pin "2") (pinfunction "2_2") (pintype "passive"))
    )
    (net (code "57") (name "Net-(LED1-K)") (class "Default")
      (node (ref "LED1") (pin "2") (pinfunction "K_2") (pintype "passive"))
      (node (ref "R1") (pin "1") (pinfunction "1_1") (pintype "passive"))
    )
    (net (code "58") (name "Net-(LED2-K)") (class "Default")
      (node (ref "LED2") (pin "2") (pinfunction "K_2") (pintype "passive"))
      (node (ref "R19") (pin "1") (pinfunction "1_1") (pintype "passive"))
    )
    (net (code "59") (name "Net-(LED3-A)") (class "Default")
      (node (ref "LED3") (pin "1") (pinfunction "A_1") (pintype "passive"))
      (node (ref "R24") (pin "2") (pinfunction "2_2") (pintype "passive"))
    )
    (net (code "60") (name "Net-(LED4-A)") (class "Default")
      (node (ref "LED4") (pin "1") (pinfunction "A_1") (pintype "passive"))
      (node (ref "R29") (pin "2") (pinfunction "2_2") (pintype "passive"))
    )
    (net (code "61") (name "Net-(LM321--IN)") (class "Default")
      (node (ref "LM321") (pin "3") (pinfunction "-IN_3") (pintype "passive"))
      (node (ref "R28") (pin "1") (pinfunction "1_1") (pintype "passive"))
      (node (ref "R30") (pin "2") (pinfunction "2_2") (pintype "passive"))
    )
    (net (code "62") (name "Net-(MCU-NRST)") (class "Default")
      (node (ref "C26") (pin "2") (pinfunction "2_2") (pintype "passive"))
      (node (ref "MCU") (pin "4") (pinfunction "NRST_4") (pintype "passive"))
    )
    (net (code "63") (name "Net-(Q1-G)") (class "Default")
      (node (ref "Q1") (pin "2") (pinfunction "G_2") (pintype "passive"))
      (node (ref "R10") (pin "1") (pinfunction "1_1") (pintype "passive"))
    )
    (net (code "64") (name "Net-(Q2-G)") (class "Default")
      (node (ref "Q2") (pin "2") (pinfunction "G_2") (pintype "passive"))
      (node (ref "R18") (pin "1") (pinfunction "1_1") (pintype "passive"))
    )
    (net (code "65") (name "Net-(Q3-G)") (class "Default")
      (node (ref "Q3") (pin "2") (pinfunction "G_2") (pintype "passive"))
      (node (ref "R11") (pin "1") (pinfunction "1_1") (pintype "passive"))
    )
    (net (code "66") (name "Net-(Q4-G)") (class "Default")
      (node (ref "Q4") (pin "2") (pinfunction "G_2") (pintype "passive"))
      (node (ref "R16") (pin "1") (pinfunction "1_1") (pintype "passive"))
    )
    (net (code "67") (name "Net-(Q5-G)") (class "Default")
      (node (ref "Q5") (pin "2") (pinfunction "G_2") (pintype "passive"))
      (node (ref "R9") (pin "1") (pinfunction "1_1") (pintype "passive"))
    )
    (net (code "68") (name "Net-(Q6-G)") (class "Default")
      (node (ref "Q6") (pin "2") (pinfunction "G_2") (pintype "passive"))
      (node (ref "R17") (pin "1") (pinfunction "1_1") (pintype "passive"))
    )
    (net (code "69") (name "Net-(XL7005A-FB)") (class "Default")
      (node (ref "C19") (pin "2") (pinfunction "2_2") (pintype "passive"))
      (node (ref "R21") (pin "2") (pinfunction "2_2") (pintype "passive"))
      (node (ref "R22") (pin "1") (pinfunction "1_1") (pintype "passive"))
      (node (ref "XL7005A") (pin "3") (pinfunction "FB_3") (pintype "passive"))
    )
    (net (code "70") (name "VBAT") (class "Default")
      (node (ref "C13") (pin "1") (pinfunction "1_1") (pintype "passive"))
      (node (ref "C16") (pin "1") (pinfunction "1_1") (pintype "passive"))
      (node (ref "C22") (pin "1") (pinfunction "1_1") (pintype "passive"))
      (node (ref "C25") (pin "1") (pinfunction "1_1") (pintype "passive"))
      (node (ref "C29") (pin "1") (pinfunction "1_1") (pintype "passive"))
      (node (ref "C4") (pin "1") (pinfunction "1_1") (pintype "passive"))
      (node (ref "C9") (pin "1") (pinfunction "1_1") (pintype "passive"))
      (node (ref "Q1") (pin "1") (pinfunction "D_1") (pintype "passive"))
      (node (ref "Q3") (pin "1") (pinfunction "D_1") (pintype "passive"))
      (node (ref "Q5") (pin "1") (pinfunction "D_1") (pintype "passive"))
      (node (ref "SW") (pin "1") (pinfunction "1_1") (pintype "passive"))
      (node (ref "V+") (pin "1") (pinfunction "1_1") (pintype "passive"))
    )
  )
)
